# NFCAccessController.net
KiCad netlist of a schematic drawn in EAGLE
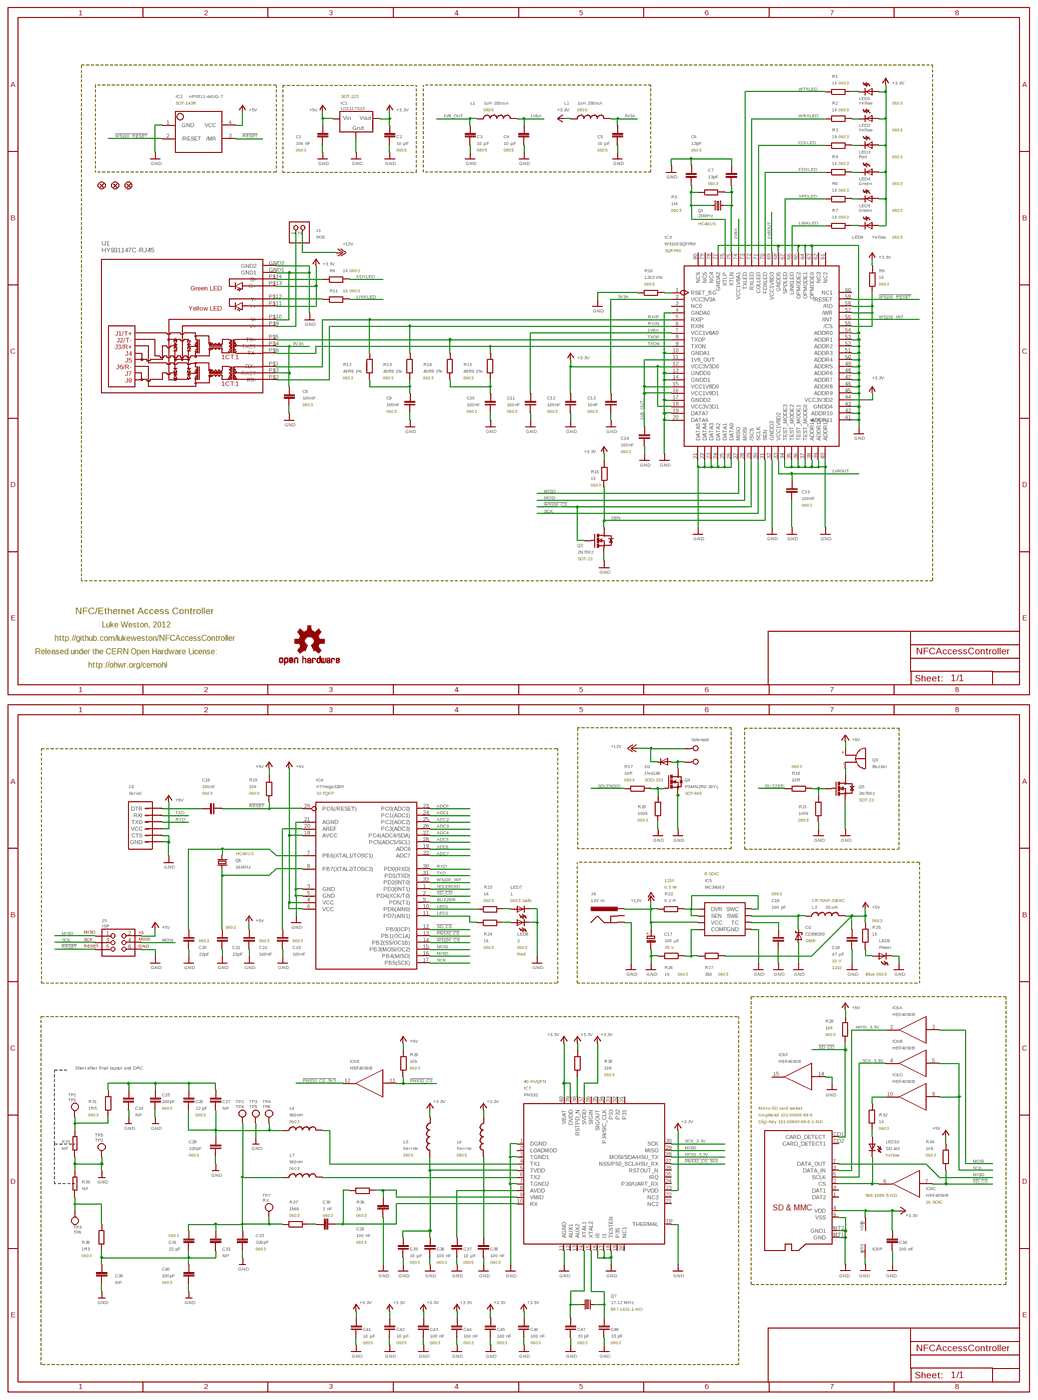
[diagram p0: schematic, sheet 1, overview]
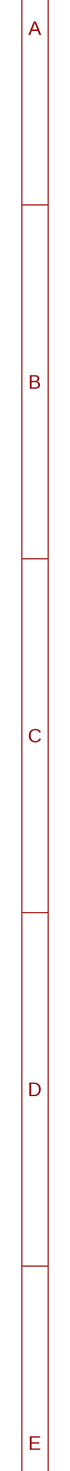
[diagram p1: schematic, sheet 1, part 1 of 4]
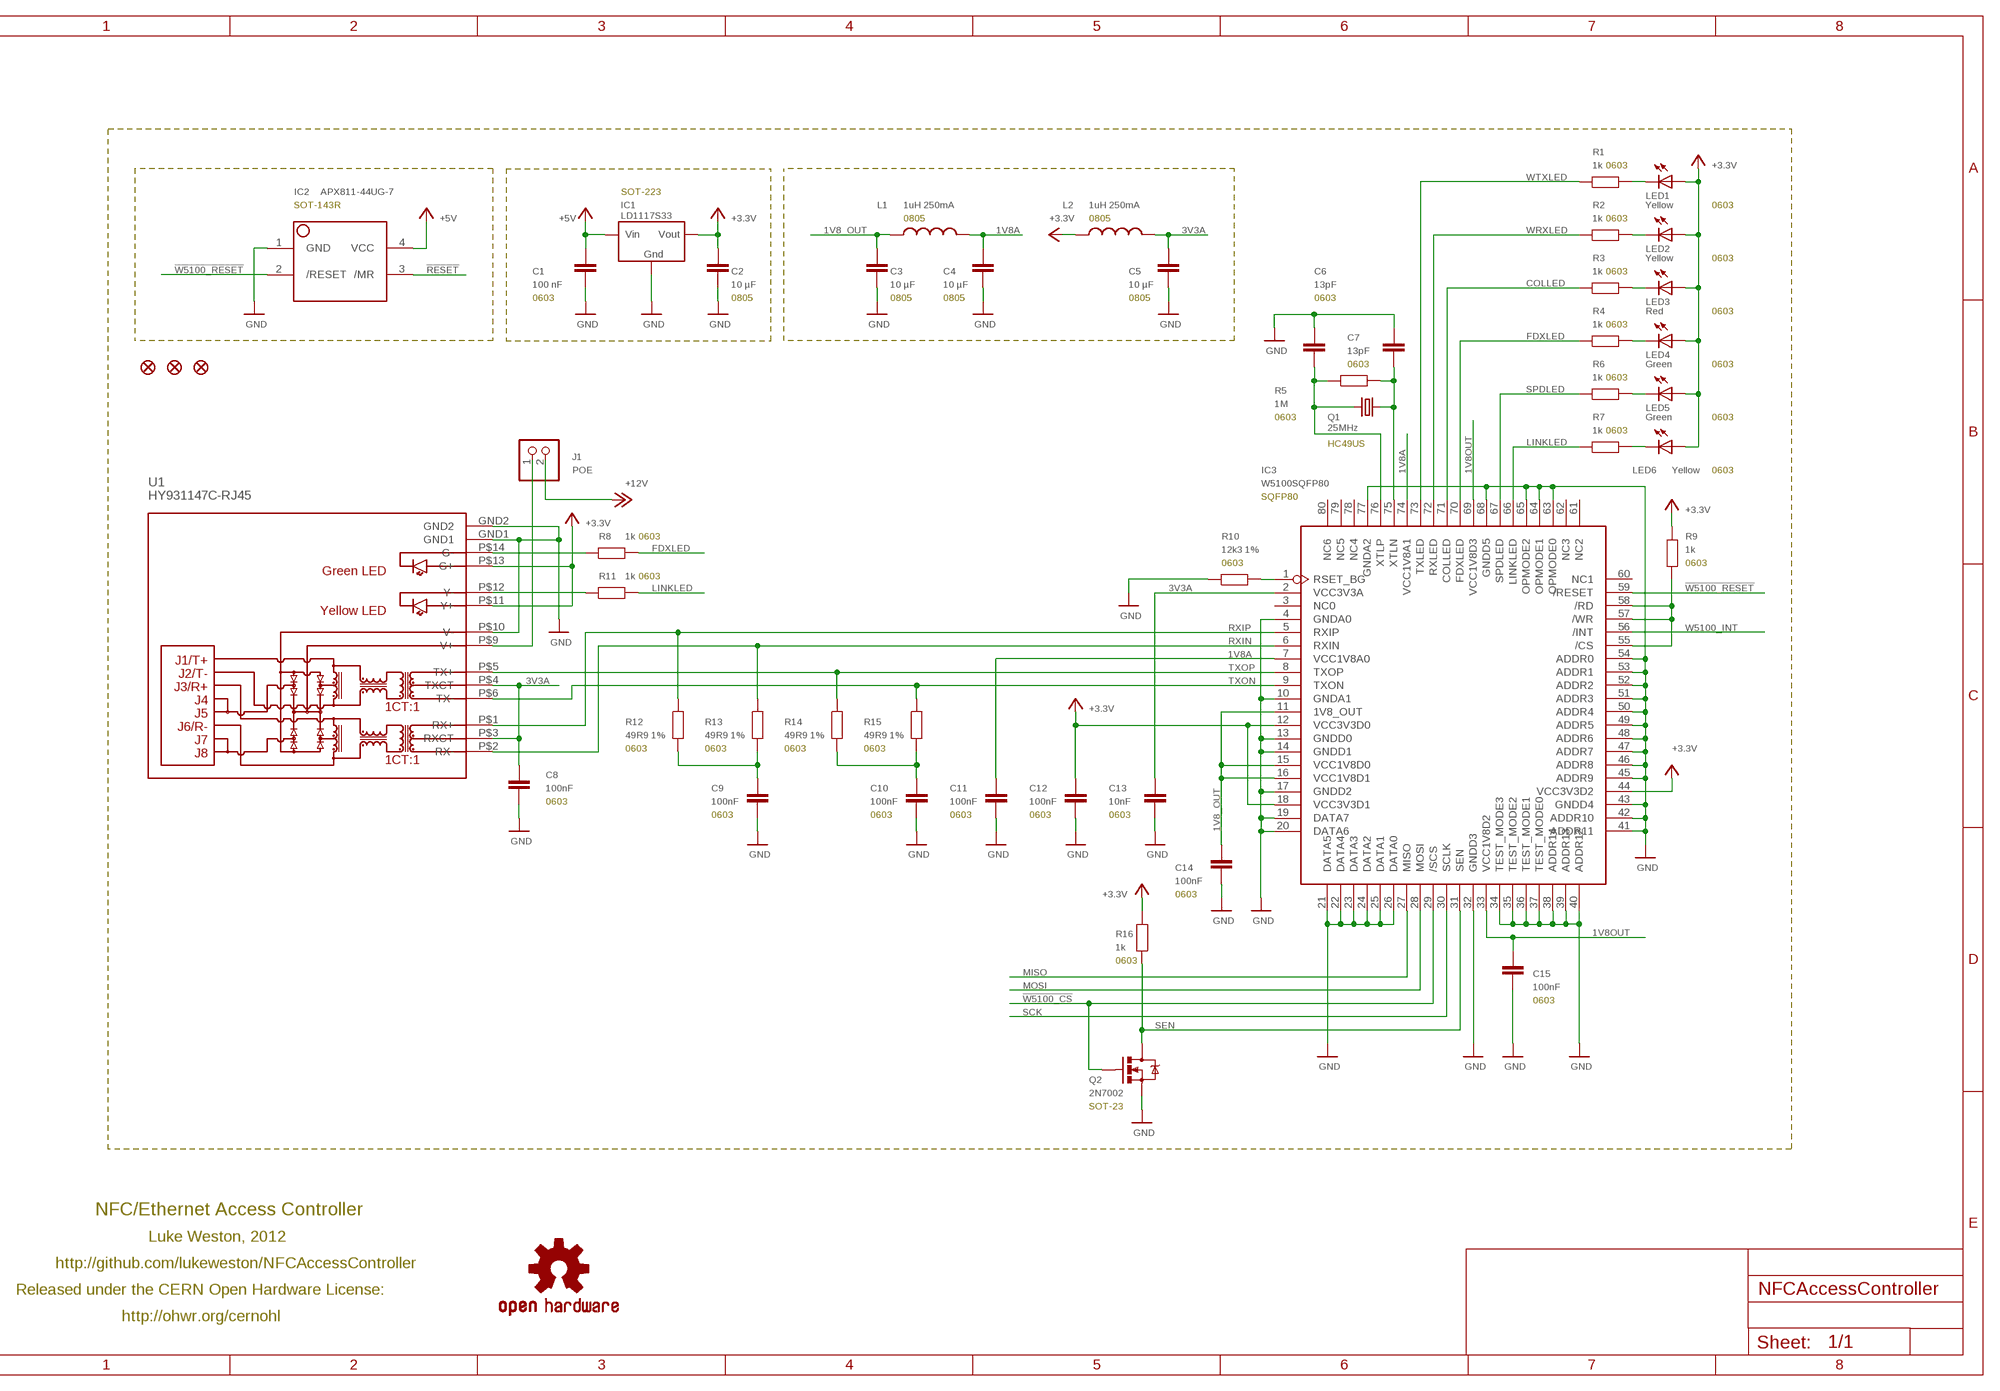
[diagram p2: schematic, sheet 1, part 2 of 4]
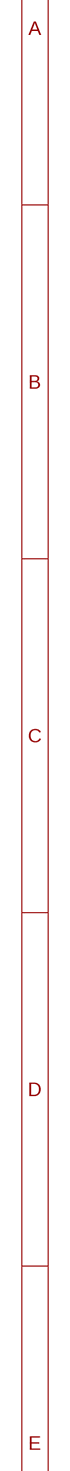
[diagram p3: schematic, sheet 1, part 3 of 4]
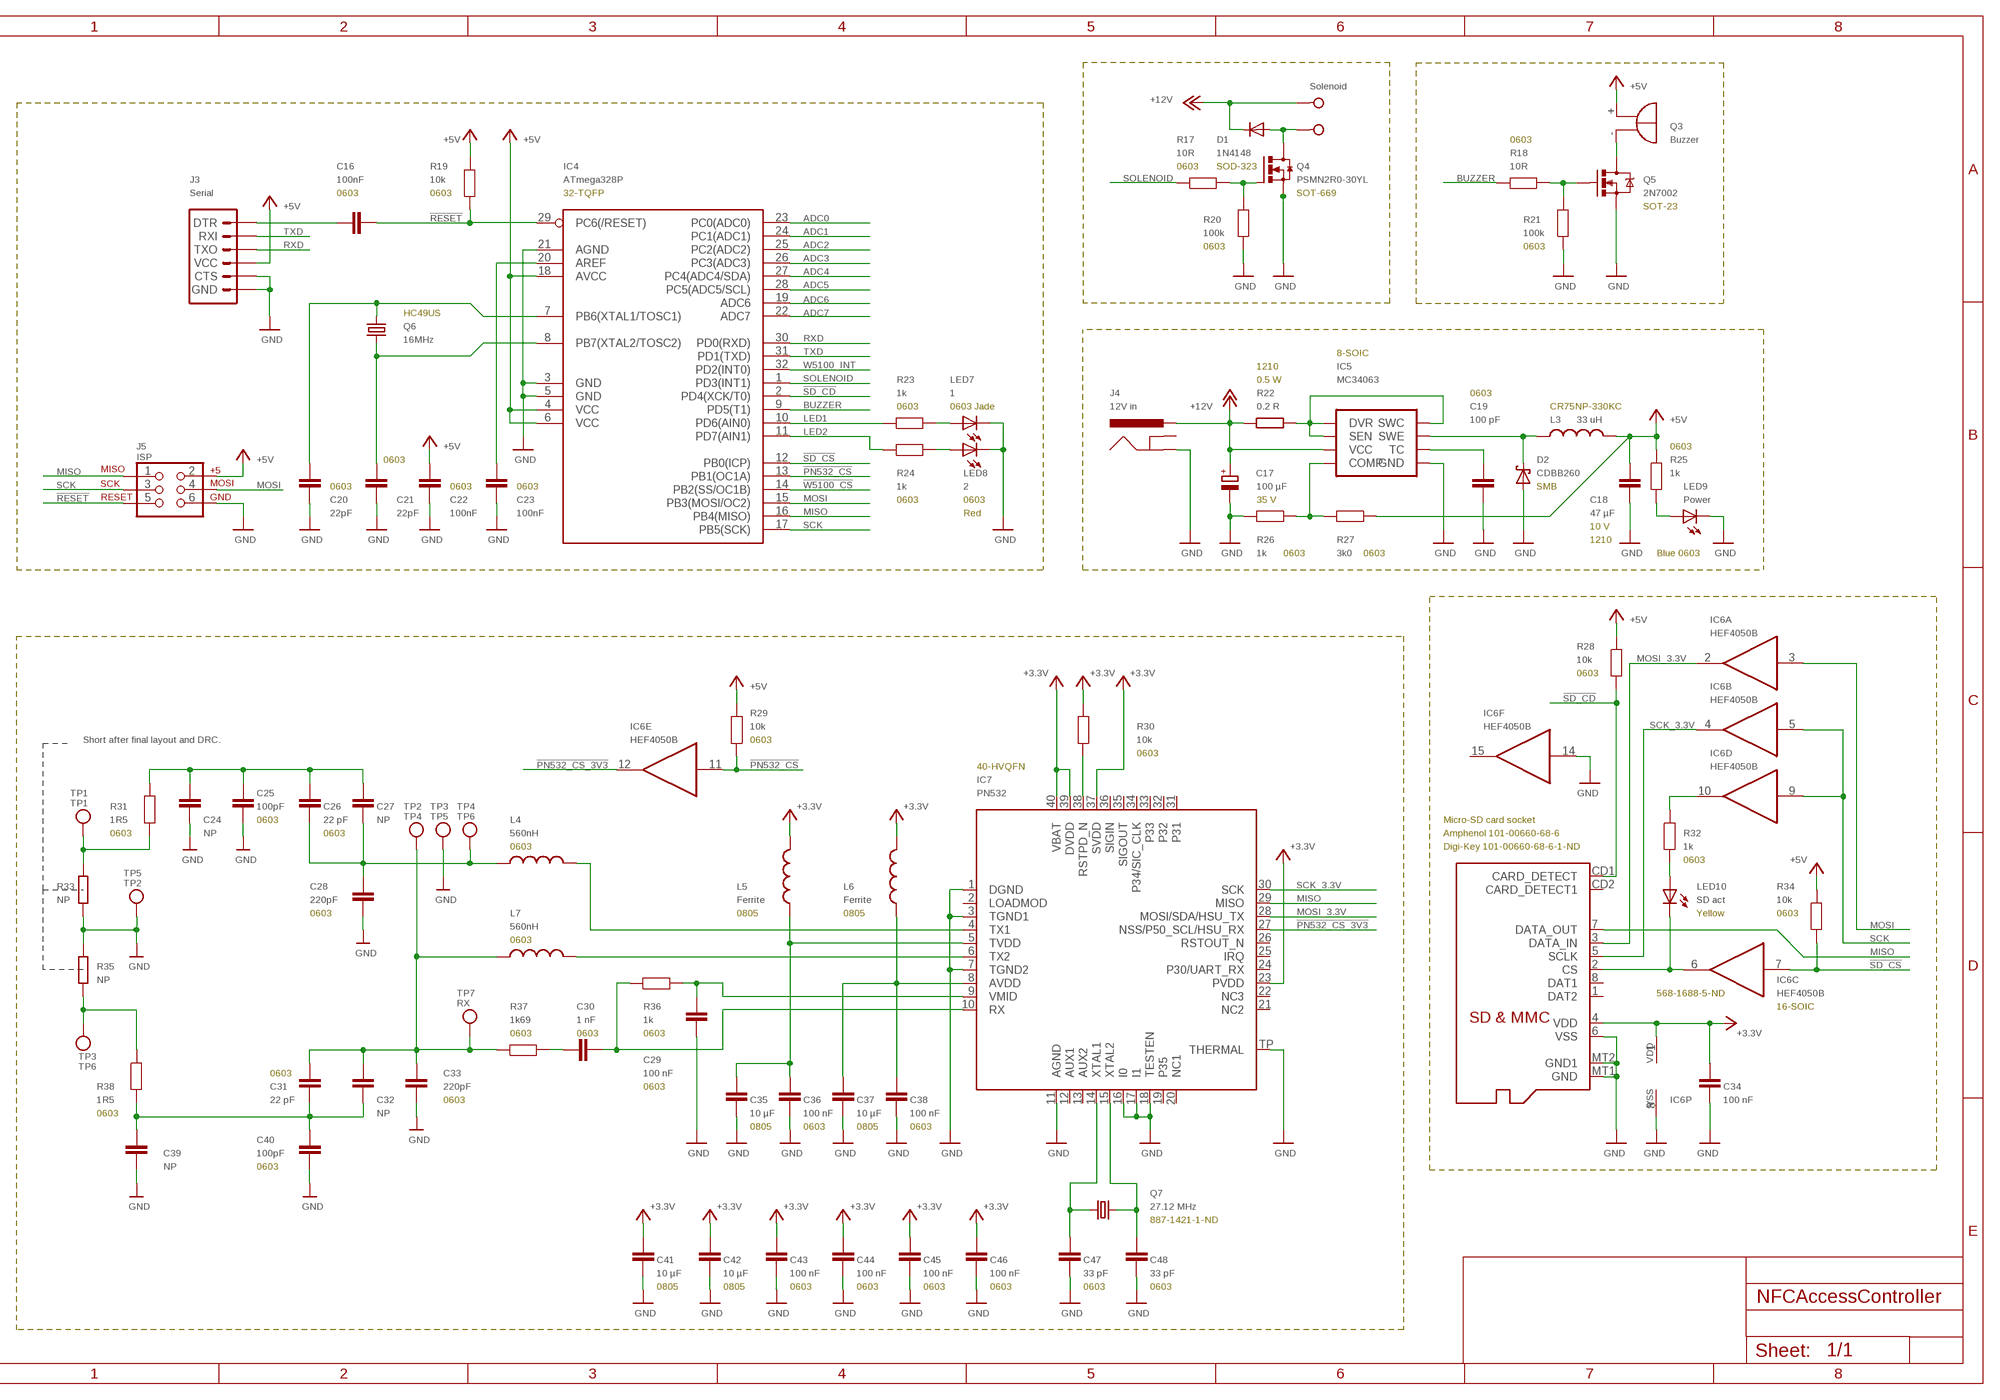
[diagram p4: schematic, sheet 1, part 4 of 4]

(export (version "E")
  (design (tool "Eeschema 10.0.6"))
  (components
    (comp (ref "C1")
      (value "100 nF")
      (footprint "eagle-import:0603")
      (libsource (lib "eagle-import") (part "CAP0603"))
    )
    (comp (ref "C2")
      (value "10 µF")
      (footprint "eagle-import:0805")
      (libsource (lib "eagle-import") (part "CAP0805"))
    )
    (comp (ref "C3")
      (value "10 µF")
      (footprint "eagle-import:0805")
      (libsource (lib "eagle-import") (part "CAP0805"))
    )
    (comp (ref "C4")
      (value "10 µF")
      (footprint "eagle-import:0805")
      (libsource (lib "eagle-import") (part "CAP0805"))
    )
    (comp (ref "C5")
      (value "10 µF")
      (footprint "eagle-import:0805")
      (libsource (lib "eagle-import") (part "CAP0805"))
    )
    (comp (ref "C6")
      (value "13pF")
      (footprint "eagle-import:0603")
      (libsource (lib "eagle-import") (part "CAP0603"))
    )
    (comp (ref "C7")
      (value "13pF")
      (footprint "eagle-import:0603")
      (libsource (lib "eagle-import") (part "CAP0603"))
    )
    (comp (ref "C8")
      (value "100nF")
      (footprint "eagle-import:0603")
      (libsource (lib "eagle-import") (part "CAP0603"))
    )
    (comp (ref "C9")
      (value "100nF")
      (footprint "eagle-import:0603")
      (libsource (lib "eagle-import") (part "CAP0603"))
    )
    (comp (ref "C10")
      (value "100nF")
      (footprint "eagle-import:0603")
      (libsource (lib "eagle-import") (part "CAP0603"))
    )
    (comp (ref "C11")
      (value "100nF")
      (footprint "eagle-import:0603")
      (libsource (lib "eagle-import") (part "CAP0603"))
    )
    (comp (ref "C12")
      (value "100nF")
      (footprint "eagle-import:0603")
      (libsource (lib "eagle-import") (part "CAP0603"))
    )
    (comp (ref "C13")
      (value "10nF")
      (footprint "eagle-import:0603")
      (libsource (lib "eagle-import") (part "CAP0603"))
    )
    (comp (ref "C14")
      (value "100nF")
      (footprint "eagle-import:0603")
      (libsource (lib "eagle-import") (part "CAP0603"))
    )
    (comp (ref "C15")
      (value "100nF")
      (footprint "eagle-import:0603")
      (libsource (lib "eagle-import") (part "CAP0603"))
    )
    (comp (ref "C16")
      (value "100nF")
      (footprint "eagle-import:0603")
      (libsource (lib "eagle-import") (part "CAP0603"))
    )
    (comp (ref "C17")
      (value "100 µF")
      (footprint "eagle-import:E2,5-6")
      (libsource (lib "eagle-import") (part "CPOL-EUE2.5-6"))
    )
    (comp (ref "C18")
      (value "47 µF")
      (footprint "eagle-import:C1210")
      (libsource (lib "eagle-import") (part "C-EUC1210"))
    )
    (comp (ref "C19")
      (value "100 pF")
      (footprint "eagle-import:0603")
      (libsource (lib "eagle-import") (part "CAP0603"))
    )
    (comp (ref "C20")
      (value "22pF")
      (footprint "eagle-import:0603")
      (libsource (lib "eagle-import") (part "CAP0603"))
    )
    (comp (ref "C21")
      (value "22pF")
      (footprint "eagle-import:0603")
      (libsource (lib "eagle-import") (part "CAP0603"))
    )
    (comp (ref "C22")
      (value "100nF")
      (footprint "eagle-import:0603")
      (libsource (lib "eagle-import") (part "CAP0603"))
    )
    (comp (ref "C23")
      (value "100nF")
      (footprint "eagle-import:0603")
      (libsource (lib "eagle-import") (part "CAP0603"))
    )
    (comp (ref "C24")
      (value "NP")
      (footprint "eagle-import:0603")
      (libsource (lib "eagle-import") (part "CAP0603"))
    )
    (comp (ref "C25")
      (value "100pF")
      (footprint "eagle-import:0603")
      (libsource (lib "eagle-import") (part "CAP0603"))
    )
    (comp (ref "C26")
      (value "22 pF")
      (footprint "eagle-import:0603")
      (libsource (lib "eagle-import") (part "CAP0603"))
    )
    (comp (ref "C27")
      (value "NP")
      (footprint "eagle-import:0603")
      (libsource (lib "eagle-import") (part "CAP0603"))
    )
    (comp (ref "C28")
      (value "220pF")
      (footprint "eagle-import:0603")
      (libsource (lib "eagle-import") (part "CAP0603"))
    )
    (comp (ref "C29")
      (value "100 nF")
      (footprint "eagle-import:0603")
      (libsource (lib "eagle-import") (part "CAP0603"))
    )
    (comp (ref "C30")
      (value "1 nF")
      (footprint "eagle-import:0603")
      (libsource (lib "eagle-import") (part "CAP0603"))
    )
    (comp (ref "C31")
      (value "22 pF")
      (footprint "eagle-import:0603")
      (libsource (lib "eagle-import") (part "CAP0603"))
    )
    (comp (ref "C32")
      (value "NP")
      (footprint "eagle-import:0603")
      (libsource (lib "eagle-import") (part "CAP0603"))
    )
    (comp (ref "C33")
      (value "220pF")
      (footprint "eagle-import:0603")
      (libsource (lib "eagle-import") (part "CAP0603"))
    )
    (comp (ref "C34")
      (value "100 nF")
      (footprint "eagle-import:0603")
      (libsource (lib "eagle-import") (part "CAP0603"))
    )
    (comp (ref "C35")
      (value "10 µF")
      (footprint "eagle-import:0805")
      (libsource (lib "eagle-import") (part "CAP0805"))
    )
    (comp (ref "C36")
      (value "100 nF")
      (footprint "eagle-import:0603")
      (libsource (lib "eagle-import") (part "CAP0603"))
    )
    (comp (ref "C37")
      (value "10 µF")
      (footprint "eagle-import:0805")
      (libsource (lib "eagle-import") (part "CAP0805"))
    )
    (comp (ref "C38")
      (value "100 nF")
      (footprint "eagle-import:0603")
      (libsource (lib "eagle-import") (part "CAP0603"))
    )
    (comp (ref "C39")
      (value "NP")
      (footprint "eagle-import:0603")
      (libsource (lib "eagle-import") (part "CAP0603"))
    )
    (comp (ref "C40")
      (value "100pF")
      (footprint "eagle-import:0603")
      (libsource (lib "eagle-import") (part "CAP0603"))
    )
    (comp (ref "C41")
      (value "10 µF")
      (footprint "eagle-import:0805")
      (libsource (lib "eagle-import") (part "CAP0805"))
    )
    (comp (ref "C42")
      (value "10 µF")
      (footprint "eagle-import:0805")
      (libsource (lib "eagle-import") (part "CAP0805"))
    )
    (comp (ref "C43")
      (value "100 nF")
      (footprint "eagle-import:0603")
      (libsource (lib "eagle-import") (part "CAP0603"))
    )
    (comp (ref "C44")
      (value "100 nF")
      (footprint "eagle-import:0603")
      (libsource (lib "eagle-import") (part "CAP0603"))
    )
    (comp (ref "C45")
      (value "100 nF")
      (footprint "eagle-import:0603")
      (libsource (lib "eagle-import") (part "CAP0603"))
    )
    (comp (ref "C46")
      (value "100 nF")
      (footprint "eagle-import:0603")
      (libsource (lib "eagle-import") (part "CAP0603"))
    )
    (comp (ref "C47")
      (value "33 pF")
      (footprint "eagle-import:0603")
      (libsource (lib "eagle-import") (part "CAP0603"))
    )
    (comp (ref "C48")
      (value "33 pF")
      (footprint "eagle-import:0603")
      (libsource (lib "eagle-import") (part "CAP0603"))
    )
    (comp (ref "D1")
      (value "1N4148")
      (footprint "eagle-import:SOD-323")
      (libsource (lib "eagle-import") (part "DIODESOD"))
    )
    (comp (ref "D2")
      (value "CDBB260")
      (footprint "eagle-import:SMB")
      (libsource (lib "eagle-import") (part "MBRS130LT3"))
    )
    (comp (ref "FID1")
      (value "FIDUCIAL1X2.5")
      (footprint "eagle-import:FIDUCIAL-1X2.5")
      (libsource (lib "eagle-import") (part "FIDUCIAL1X2.5"))
    )
    (comp (ref "FID2")
      (value "FIDUCIAL1X2.5")
      (footprint "eagle-import:FIDUCIAL-1X2.5")
      (libsource (lib "eagle-import") (part "FIDUCIAL1X2.5"))
    )
    (comp (ref "FID3")
      (value "FIDUCIAL1X2.5")
      (footprint "eagle-import:FIDUCIAL-1X2.5")
      (libsource (lib "eagle-import") (part "FIDUCIAL1X2.5"))
    )
    (comp (ref "IC1")
      (value "LD1117S33")
      (footprint "eagle-import:SOT223")
      (fields
        (field (name "MPN") "REG1117")
        (field (name "MPN_1") "REG1117")
        (field (name "OC_FARNELL") "1097566")
        (field (name "OC_NEWARK") "14P6981")
      )
      (libsource (lib "eagle-import") (part "REG1117"))
    )
    (comp (ref "IC2")
      (value "APX811-44UG-7")
      (footprint "eagle-import:SOT143-R")
      (libsource (lib "eagle-import") (part "APX81X-RESET-IC"))
    )
    (comp (ref "IC3")
      (value "W5100SQFP80")
      (footprint "eagle-import:SQFP80")
      (libsource (lib "eagle-import") (part "W5100SQFP80"))
    )
    (comp (ref "IC4")
      (value "ATmega328P")
      (footprint "eagle-import:TQFP32-08")
      (libsource (lib "eagle-import") (part "AVR-MEGA8-AI"))
    )
    (comp (ref "IC5")
      (value "MC34063")
      (footprint "eagle-import:SO08")
      (libsource (lib "eagle-import") (part "MC34063SMD"))
    )
    (comp (ref "IC6")
      (value "HEF4050B")
      (footprint "eagle-import:SO16")
      (libsource (lib "eagle-import") (part "4050D"))
    )
    (comp (ref "IC7")
      (value "PN532")
      (footprint "eagle-import:HVQFN40-6X6")
      (libsource (lib "eagle-import") (part "PN532"))
    )
    (comp (ref "J1")
      (value "POE")
      (footprint "eagle-import:1X02")
      (libsource (lib "eagle-import") (part "PINHD-1X2"))
    )
    (comp (ref "J2")
      (value "Solenoid")
      (footprint "eagle-import:W237-132")
      (fields (field (name "OC_FARNELL") "unknown") (field (name "OC_NEWARK") "unknown"))
      (libsource (lib "eagle-import") (part "W237-02P"))
    )
    (comp (ref "J3")
      (value "Serial")
      (footprint "eagle-import:1X06_LONGPADS")
      (libsource (lib "eagle-import") (part "ARDUINO_SERIAL_PROGRAMLONGPADS"))
    )
    (comp (ref "J4")
      (value "12V in")
      (footprint "eagle-import:POWER_JACK_SLOT")
      (libsource (lib "eagle-import") (part "POWER_JACKSLT"))
    )
    (comp (ref "J5")
      (value "ISP")
      (footprint "eagle-import:2X3-NS")
      (libsource (lib "eagle-import") (part "AVR_SPI_PRG_6NS"))
    )
    (comp (ref "J6")
      (value "MicroSD Card")
      (footprint "eagle-import:ADAFRUIT_MICROSD")
      (libsource (lib "eagle-import") (part "ADAFRUIT_MICROSD"))
    )
    (comp (ref "L1")
      (value "1uH 250mA")
      (footprint "eagle-import:L2012C")
      (libsource (lib "eagle-import") (part "L-USL2012C"))
    )
    (comp (ref "L2")
      (value "1uH 250mA")
      (footprint "eagle-import:L2012C")
      (libsource (lib "eagle-import") (part "L-USL2012C"))
    )
    (comp (ref "L3")
      (value "33 uH")
      (footprint "eagle-import:CR75")
      (libsource (lib "eagle-import") (part "INDUCTORCR75"))
    )
    (comp (ref "L4")
      (value "560nH")
      (footprint "eagle-import:0603")
      (libsource (lib "eagle-import") (part "microbuilder_INDUCTOR0603"))
    )
    (comp (ref "L5")
      (value "Ferrite")
      (footprint "eagle-import:0805-LARGE")
      (libsource (lib "eagle-import") (part "INDUCTOR0805-LARGE"))
    )
    (comp (ref "L6")
      (value "Ferrite")
      (footprint "eagle-import:0805-LARGE")
      (libsource (lib "eagle-import") (part "INDUCTOR0805-LARGE"))
    )
    (comp (ref "L7")
      (value "560nH")
      (footprint "eagle-import:0603")
      (libsource (lib "eagle-import") (part "microbuilder_INDUCTOR0603"))
    )
    (comp (ref "LED1")
      (value "Yellow")
      (footprint "eagle-import:LED-0603")
      (libsource (lib "eagle-import") (part "LED0603"))
    )
    (comp (ref "LED2")
      (value "Yellow")
      (footprint "eagle-import:LED-0603")
      (libsource (lib "eagle-import") (part "LED0603"))
    )
    (comp (ref "LED3")
      (value "Red")
      (footprint "eagle-import:LED-0603")
      (libsource (lib "eagle-import") (part "LED0603"))
    )
    (comp (ref "LED4")
      (value "Green")
      (footprint "eagle-import:LED-0603")
      (libsource (lib "eagle-import") (part "LED0603"))
    )
    (comp (ref "LED5")
      (value "Green")
      (footprint "eagle-import:LED-0603")
      (libsource (lib "eagle-import") (part "LED0603"))
    )
    (comp (ref "LED6")
      (value "Yellow")
      (footprint "eagle-import:LED-0603")
      (libsource (lib "eagle-import") (part "LED0603"))
    )
    (comp (ref "LED7")
      (value "1")
      (footprint "eagle-import:LED-0603")
      (libsource (lib "eagle-import") (part "LED0603"))
    )
    (comp (ref "LED8")
      (value "2")
      (footprint "eagle-import:LED-0603")
      (libsource (lib "eagle-import") (part "LED0603"))
    )
    (comp (ref "LED9")
      (value "Power")
      (footprint "eagle-import:LED-0603")
      (libsource (lib "eagle-import") (part "LED0603"))
    )
    (comp (ref "LED10")
      (value "SD act")
      (footprint "eagle-import:LED-0603")
      (libsource (lib "eagle-import") (part "LED0603"))
    )
    (comp (ref "Q1")
      (value "25MHz")
      (footprint "eagle-import:HC49U-V")
      (libsource (lib "eagle-import") (part "freetronics-master-v1_CRYSTALHC49UV"))
    )
    (comp (ref "Q2")
      (value "2N7002")
      (footprint "eagle-import:SOT23-3")
      (libsource (lib "eagle-import") (part "MOSFET-NCHANNELSMD"))
    )
    (comp (ref "Q3")
      (value "Buzzer")
      (footprint "eagle-import:F_TMB")
      (libsource (lib "eagle-import") (part "F/TMB"))
    )
    (comp (ref "Q4")
      (value "PSMN2R0-30YL")
      (footprint "eagle-import:SOT669")
      (libsource (lib "eagle-import") (part "PH7030L"))
    )
    (comp (ref "Q5")
      (value "2N7002")
      (footprint "eagle-import:SOT23-3")
      (libsource (lib "eagle-import") (part "freetronics-master-v1_MOSFET-NCHANNELSMD"))
    )
    (comp (ref "Q6")
      (value "16MHz")
      (footprint "eagle-import:HC49U-V")
      (libsource (lib "eagle-import") (part "freetronics-master-v1_CRYSTALHC49UV"))
    )
    (comp (ref "Q7")
      (value "27.12 MHz")
      (footprint "eagle-import:CRYSTAL-SMD-5X3")
      (libsource (lib "eagle-import") (part "CRYSTAL5X3"))
    )
    (comp (ref "R1")
      (value "1k")
      (footprint "eagle-import:0603")
      (libsource (lib "eagle-import") (part "RESISTOR0603"))
    )
    (comp (ref "R2")
      (value "1k")
      (footprint "eagle-import:0603")
      (libsource (lib "eagle-import") (part "RESISTOR0603"))
    )
    (comp (ref "R3")
      (value "1k")
      (footprint "eagle-import:0603")
      (libsource (lib "eagle-import") (part "RESISTOR0603"))
    )
    (comp (ref "R4")
      (value "1k")
      (footprint "eagle-import:0603")
      (libsource (lib "eagle-import") (part "RESISTOR0603"))
    )
    (comp (ref "R5")
      (value "1M")
      (footprint "eagle-import:0603")
      (libsource (lib "eagle-import") (part "RESISTOR0603"))
    )
    (comp (ref "R6")
      (value "1k")
      (footprint "eagle-import:0603")
      (libsource (lib "eagle-import") (part "RESISTOR0603"))
    )
    (comp (ref "R7")
      (value "1k")
      (footprint "eagle-import:0603")
      (libsource (lib "eagle-import") (part "RESISTOR0603"))
    )
    (comp (ref "R8")
      (value "1k")
      (footprint "eagle-import:0603")
      (libsource (lib "eagle-import") (part "RESISTOR0603"))
    )
    (comp (ref "R9")
      (value "1k")
      (footprint "eagle-import:0603")
      (libsource (lib "eagle-import") (part "RESISTOR0603"))
    )
    (comp (ref "R10")
      (value "12k3 1%")
      (footprint "eagle-import:0603")
      (libsource (lib "eagle-import") (part "RESISTOR0603"))
    )
    (comp (ref "R11")
      (value "1k")
      (footprint "eagle-import:0603")
      (libsource (lib "eagle-import") (part "RESISTOR0603"))
    )
    (comp (ref "R12")
      (value "49R9 1%")
      (footprint "eagle-import:0603")
      (libsource (lib "eagle-import") (part "RESISTOR0603"))
    )
    (comp (ref "R13")
      (value "49R9 1%")
      (footprint "eagle-import:0603")
      (libsource (lib "eagle-import") (part "RESISTOR0603"))
    )
    (comp (ref "R14")
      (value "49R9 1%")
      (footprint "eagle-import:0603")
      (libsource (lib "eagle-import") (part "RESISTOR0603"))
    )
    (comp (ref "R15")
      (value "49R9 1%")
      (footprint "eagle-import:0603")
      (libsource (lib "eagle-import") (part "RESISTOR0603"))
    )
    (comp (ref "R16")
      (value "1k")
      (footprint "eagle-import:0603")
      (libsource (lib "eagle-import") (part "RESISTOR0603"))
    )
    (comp (ref "R17")
      (value "10R")
      (footprint "eagle-import:0603")
      (libsource (lib "eagle-import") (part "RESISTOR0603"))
    )
    (comp (ref "R18")
      (value "10R")
      (footprint "eagle-import:0603")
      (libsource (lib "eagle-import") (part "RESISTOR0603"))
    )
    (comp (ref "R19")
      (value "10k")
      (footprint "eagle-import:0603")
      (libsource (lib "eagle-import") (part "RESISTOR0603"))
    )
    (comp (ref "R20")
      (value "100k")
      (footprint "eagle-import:0603")
      (libsource (lib "eagle-import") (part "RESISTOR0603"))
    )
    (comp (ref "R21")
      (value "100k")
      (footprint "eagle-import:0603")
      (libsource (lib "eagle-import") (part "RESISTOR0603"))
    )
    (comp (ref "R22")
      (value "0.2 R")
      (footprint "eagle-import:R1210")
      (libsource (lib "eagle-import") (part "R-EU_R1210"))
    )
    (comp (ref "R23")
      (value "1k")
      (footprint "eagle-import:0603")
      (libsource (lib "eagle-import") (part "RESISTOR0603"))
    )
    (comp (ref "R24")
      (value "1k")
      (footprint "eagle-import:0603")
      (libsource (lib "eagle-import") (part "RESISTOR0603"))
    )
    (comp (ref "R25")
      (value "1k")
      (footprint "eagle-import:0603")
      (libsource (lib "eagle-import") (part "RESISTOR0603"))
    )
    (comp (ref "R26")
      (value "1k")
      (footprint "eagle-import:0603")
      (libsource (lib "eagle-import") (part "RESISTOR0603"))
    )
    (comp (ref "R27")
      (value "3k0")
      (footprint "eagle-import:0603")
      (libsource (lib "eagle-import") (part "RESISTOR0603"))
    )
    (comp (ref "R28")
      (value "10k")
      (footprint "eagle-import:0603")
      (libsource (lib "eagle-import") (part "RESISTOR0603"))
    )
    (comp (ref "R29")
      (value "10k")
      (footprint "eagle-import:0603")
      (libsource (lib "eagle-import") (part "RESISTOR0603"))
    )
    (comp (ref "R30")
      (value "10k")
      (footprint "eagle-import:0603")
      (libsource (lib "eagle-import") (part "RESISTOR0603"))
    )
    (comp (ref "R31")
      (value "1R5")
      (footprint "eagle-import:0603")
      (libsource (lib "eagle-import") (part "RESISTOR0603"))
    )
    (comp (ref "R32")
      (value "1k")
      (footprint "eagle-import:0603")
      (libsource (lib "eagle-import") (part "RESISTOR0603"))
    )
    (comp (ref "R33")
      (value "NP")
      (footprint "eagle-import:R0201")
      (libsource (lib "eagle-import") (part "R-EU_R0201"))
    )
    (comp (ref "R34")
      (value "10k")
      (footprint "eagle-import:0603")
      (libsource (lib "eagle-import") (part "RESISTOR0603"))
    )
    (comp (ref "R35")
      (value "NP")
      (footprint "eagle-import:R0201")
      (libsource (lib "eagle-import") (part "R-EU_R0201"))
    )
    (comp (ref "R36")
      (value "1k")
      (footprint "eagle-import:0603")
      (libsource (lib "eagle-import") (part "RESISTOR0603"))
    )
    (comp (ref "R37")
      (value "1k69")
      (footprint "eagle-import:0603")
      (libsource (lib "eagle-import") (part "RESISTOR0603"))
    )
    (comp (ref "R38")
      (value "1R5")
      (footprint "eagle-import:0603")
      (libsource (lib "eagle-import") (part "RESISTOR0603"))
    )
    (comp (ref "S$1")
      (value "OSHW-LOGOS")
      (footprint "eagle-import:OSHW-LOGO-S")
      (libsource (lib "eagle-import") (part "OSHW-LOGOS"))
    )
    (comp (ref "TP1")
      (value "TP1")
      (footprint "eagle-import:TESTPOINT_PAD_2MM")
      (libsource (lib "eagle-import") (part "TESTPOINTPAD"))
    )
    (comp (ref "TP2")
      (value "TP4")
      (footprint "eagle-import:TESTPOINT_PAD_2MM")
      (libsource (lib "eagle-import") (part "TESTPOINTPAD"))
    )
    (comp (ref "TP3")
      (value "TP5")
      (footprint "eagle-import:TESTPOINT_PAD_2MM")
      (libsource (lib "eagle-import") (part "TESTPOINTPAD"))
    )
    (comp (ref "TP4")
      (value "TP6")
      (footprint "eagle-import:TESTPOINT_PAD_2MM")
      (libsource (lib "eagle-import") (part "TESTPOINTPAD"))
    )
    (comp (ref "TP5")
      (value "TP2")
      (footprint "eagle-import:TESTPOINT_PAD_2MM")
      (libsource (lib "eagle-import") (part "TESTPOINTPAD"))
    )
    (comp (ref "TP6")
      (value "TP3")
      (footprint "eagle-import:TESTPOINT_PAD_2MM")
      (libsource (lib "eagle-import") (part "TESTPOINTPAD"))
    )
    (comp (ref "TP7")
      (value "RX")
      (footprint "eagle-import:TESTPOINT_PAD_2MM")
      (libsource (lib "eagle-import") (part "TESTPOINTPAD"))
    )
    (comp (ref "U1")
      (value "HY931147C-RJ45")
      (footprint "eagle-import:HY931147C")
      (libsource (lib "eagle-import") (part "HY931147C-RJ45"))
    )
  )
  (nets
    (net (code "1") (name "+3.3V") (class "Default")
      (node (ref "C12") (pin "1") (pinfunction "1_1") (pintype "passive"))
      (node (ref "C2") (pin "1") (pinfunction "1_1") (pintype "passive"))
      (node (ref "C34") (pin "1") (pinfunction "1_1") (pintype "passive"))
      (node (ref "C41") (pin "1") (pinfunction "1_1") (pintype "passive"))
      (node (ref "C42") (pin "1") (pinfunction "1_1") (pintype "passive"))
      (node (ref "C43") (pin "1") (pinfunction "1_1") (pintype "passive"))
      (node (ref "C44") (pin "1") (pinfunction "1_1") (pintype "passive"))
      (node (ref "C45") (pin "1") (pinfunction "1_1") (pintype "passive"))
      (node (ref "C46") (pin "1") (pinfunction "1_1") (pintype "passive"))
      (node (ref "IC1") (pin "2") (pinfunction "VOUT_2") (pintype "output"))
      (node (ref "IC3") (pin "12") (pinfunction "VCC3V3D0_12") (pintype "bidirectional"))
      (node (ref "IC3") (pin "18") (pinfunction "VCC3V3D1_18") (pintype "bidirectional"))
      (node (ref "IC3") (pin "44") (pinfunction "VCC3V3D2_44") (pintype "bidirectional"))
      (node (ref "IC6") (pin "1") (pinfunction "VDD_1") (pintype "power_in"))
      (node (ref "IC7") (pin "23") (pinfunction "PVDD_23") (pintype "bidirectional"))
      (node (ref "IC7") (pin "37") (pinfunction "SVDD_37") (pintype "bidirectional"))
      (node (ref "IC7") (pin "39") (pinfunction "DVDD_39") (pintype "bidirectional"))
      (node (ref "IC7") (pin "40") (pinfunction "VBAT_40") (pintype "bidirectional"))
      (node (ref "J6") (pin "4") (pinfunction "VDD_4") (pintype "power_in"))
      (node (ref "L2") (pin "1") (pinfunction "1_1") (pintype "passive"))
      (node (ref "L5") (pin "2") (pinfunction "2_2") (pintype "passive"))
      (node (ref "L6") (pin "2") (pinfunction "2_2") (pintype "passive"))
      (node (ref "LED1") (pin "A") (pinfunction "A_A") (pintype "passive"))
      (node (ref "LED2") (pin "A") (pinfunction "A_A") (pintype "passive"))
      (node (ref "LED3") (pin "A") (pinfunction "A_A") (pintype "passive"))
      (node (ref "LED4") (pin "A") (pinfunction "A_A") (pintype "passive"))
      (node (ref "LED5") (pin "A") (pinfunction "A_A") (pintype "passive"))
      (node (ref "LED6") (pin "A") (pinfunction "A_A") (pintype "passive"))
      (node (ref "R16") (pin "1") (pinfunction "1_1") (pintype "passive"))
      (node (ref "R30") (pin "1") (pinfunction "1_1") (pintype "passive"))
      (node (ref "R9") (pin "1") (pinfunction "1_1") (pintype "passive"))
      (node (ref "U1") (pin "P$11") (pinfunction "Y+_P$11") (pintype "bidirectional"))
      (node (ref "U1") (pin "P$13") (pinfunction "G+_P$13") (pintype "bidirectional"))
    )
    (net (code "2") (name "+5V") (class "Default")
      (node (ref "C1") (pin "1") (pinfunction "1_1") (pintype "passive"))
      (node (ref "C18") (pin "1") (pinfunction "1_1") (pintype "passive"))
      (node (ref "C22") (pin "1") (pinfunction "1_1") (pintype "passive"))
      (node (ref "IC1") (pin "3") (pinfunction "VIN_3") (pintype "input"))
      (node (ref "IC2") (pin "4") (pinfunction "VCC_4") (pintype "power_in"))
      (node (ref "IC4") (pin "18") (pinfunction "AVCC_18") (pintype "bidirectional"))
      (node (ref "IC4") (pin "4") (pinfunction "VCC_4") (pintype "bidirectional"))
      (node (ref "IC4") (pin "6") (pinfunction "VCC_6") (pintype "bidirectional"))
      (node (ref "J3") (pin "4") (pinfunction "VCC_4") (pintype "passive"))
      (node (ref "J5") (pin "2") (pinfunction "2_2") (pintype "passive"))
      (node (ref "L3") (pin "P$2") (pinfunction "2_P$2") (pintype "passive"))
      (node (ref "Q3") (pin "+") (pinfunction "+_+") (pintype "passive"))
      (node (ref "R19") (pin "2") (pinfunction "2_2") (pintype "passive"))
      (node (ref "R25") (pin "2") (pinfunction "2_2") (pintype "passive"))
      (node (ref "R27") (pin "1") (pinfunction "1_1") (pintype "passive"))
      (node (ref "R28") (pin "2") (pinfunction "2_2") (pintype "passive"))
      (node (ref "R29") (pin "1") (pinfunction "1_1") (pintype "passive"))
      (node (ref "R34") (pin "2") (pinfunction "2_2") (pintype "passive"))
    )
    (net (code "3") (name "+12V") (class "Default")
      (node (ref "C17") (pin "+") (pinfunction "+_+") (pintype "passive"))
      (node (ref "D1") (pin "1") (pinfunction "C_1") (pintype "passive"))
      (node (ref "IC5") (pin "6") (pinfunction "VCC_6") (pintype "bidirectional"))
      (node (ref "J1") (pin "2") (pinfunction "2_2") (pintype "passive"))
      (node (ref "J2") (pin "1") (pinfunction "KL_1") (pintype "passive"))
      (node (ref "J4") (pin "PWR") (pinfunction "PWR_PWR") (pintype "bidirectional"))
      (node (ref "R22") (pin "1") (pinfunction "1_1") (pintype "passive"))
    )
    (net (code "4") (name "/1V8A") (class "Default")
      (node (ref "C11") (pin "1") (pinfunction "1_1") (pintype "passive"))
      (node (ref "C4") (pin "1") (pinfunction "1_1") (pintype "passive"))
      (node (ref "IC3") (pin "7") (pinfunction "VCC1V8A0_7") (pintype "bidirectional"))
      (node (ref "IC3") (pin "74") (pinfunction "VCC1V8A1_74") (pintype "bidirectional"))
      (node (ref "L1") (pin "2") (pinfunction "2_2") (pintype "passive"))
    )
    (net (code "5") (name "/1V8OUT") (class "Default")
      (node (ref "C15") (pin "1") (pinfunction "1_1") (pintype "passive"))
      (node (ref "IC3") (pin "33") (pinfunction "VCC1V8D2_33") (pintype "bidirectional"))
      (node (ref "IC3") (pin "69") (pinfunction "VCC1V8D3_69") (pintype "bidirectional"))
    )
    (net (code "6") (name "/1V8_OUT") (class "Default")
      (node (ref "C14") (pin "1") (pinfunction "1_1") (pintype "passive"))
      (node (ref "C3") (pin "1") (pinfunction "1_1") (pintype "passive"))
      (node (ref "IC3") (pin "11") (pinfunction "1V8_OUT_11") (pintype "bidirectional"))
      (node (ref "IC3") (pin "15") (pinfunction "VCC1V8D0_15") (pintype "bidirectional"))
      (node (ref "IC3") (pin "16") (pinfunction "VCC1V8D1_16") (pintype "bidirectional"))
      (node (ref "L1") (pin "1") (pinfunction "1_1") (pintype "passive"))
    )
    (net (code "7") (name "/3V3A") (class "Default")
      (node (ref "C13") (pin "1") (pinfunction "1_1") (pintype "passive"))
      (node (ref "C5") (pin "1") (pinfunction "1_1") (pintype "passive"))
      (node (ref "C8") (pin "1") (pinfunction "1_1") (pintype "passive"))
      (node (ref "IC3") (pin "2") (pinfunction "VCC3V3A_2") (pintype "bidirectional"))
      (node (ref "L2") (pin "2") (pinfunction "2_2") (pintype "passive"))
      (node (ref "U1") (pin "P$3") (pinfunction "RXCT_P$3") (pintype "bidirectional"))
      (node (ref "U1") (pin "P$4") (pinfunction "TXCT_P$4") (pintype "bidirectional"))
    )
    (net (code "8") (name "/ADC0") (class "Default")
      (node (ref "IC4") (pin "23") (pinfunction "PC0(ADC0)_23") (pintype "bidirectional"))
    )
    (net (code "9") (name "/ADC1") (class "Default")
      (node (ref "IC4") (pin "24") (pinfunction "PC1(ADC1)_24") (pintype "bidirectional"))
    )
    (net (code "10") (name "/ADC2") (class "Default")
      (node (ref "IC4") (pin "25") (pinfunction "PC2(ADC2)_25") (pintype "bidirectional"))
    )
    (net (code "11") (name "/ADC3") (class "Default")
      (node (ref "IC4") (pin "26") (pinfunction "PC3(ADC3)_26") (pintype "bidirectional"))
    )
    (net (code "12") (name "/ADC4") (class "Default")
      (node (ref "IC4") (pin "27") (pinfunction "PC4(ADC4/SDA)_27") (pintype "bidirectional"))
    )
    (net (code "13") (name "/ADC5") (class "Default")
      (node (ref "IC4") (pin "28") (pinfunction "PC5(ADC5/SCL)_28") (pintype "bidirectional"))
    )
    (net (code "14") (name "/ADC6") (class "Default")
      (node (ref "IC4") (pin "19") (pinfunction "ADC6_19") (pintype "bidirectional"))
    )
    (net (code "15") (name "/ADC7") (class "Default")
      (node (ref "IC4") (pin "22") (pinfunction "ADC7_22") (pintype "bidirectional"))
    )
    (net (code "16") (name "/BUZZER") (class "Default")
      (node (ref "IC4") (pin "9") (pinfunction "PD5(T1)_9") (pintype "bidirectional"))
      (node (ref "R18") (pin "1") (pinfunction "1_1") (pintype "passive"))
    )
    (net (code "17") (name "/COLLED") (class "Default")
      (node (ref "IC3") (pin "71") (pinfunction "COLLED_71") (pintype "bidirectional"))
      (node (ref "R3") (pin "1") (pinfunction "1_1") (pintype "passive"))
    )
    (net (code "18") (name "/FDXLED") (class "Default")
      (node (ref "IC3") (pin "70") (pinfunction "FDXLED_70") (pintype "bidirectional"))
      (node (ref "R4") (pin "1") (pinfunction "1_1") (pintype "passive"))
      (node (ref "R8") (pin "2") (pinfunction "2_2") (pintype "passive"))
    )
    (net (code "19") (name "/LED1") (class "Default")
      (node (ref "IC4") (pin "10") (pinfunction "PD6(AIN0)_10") (pintype "bidirectional"))
      (node (ref "R23") (pin "1") (pinfunction "1_1") (pintype "passive"))
    )
    (net (code "20") (name "/LED2") (class "Default")
      (node (ref "IC4") (pin "11") (pinfunction "PD7(AIN1)_11") (pintype "bidirectional"))
      (node (ref "R24") (pin "1") (pinfunction "1_1") (pintype "passive"))
    )
    (net (code "21") (name "/LINKLED") (class "Default")
      (node (ref "IC3") (pin "66") (pinfunction "LINKLED_66") (pintype "bidirectional"))
      (node (ref "R11") (pin "2") (pinfunction "2_2") (pintype "passive"))
      (node (ref "R7") (pin "1") (pinfunction "1_1") (pintype "passive"))
    )
    (net (code "22") (name "/MISO") (class "Default")
      (node (ref "IC3") (pin "27") (pinfunction "MISO_27") (pintype "bidirectional"))
      (node (ref "IC4") (pin "16") (pinfunction "PB4(MISO)_16") (pintype "bidirectional"))
      (node (ref "IC7") (pin "29") (pinfunction "MISO_29") (pintype "bidirectional"))
      (node (ref "J5") (pin "1") (pinfunction "1_1") (pintype "passive"))
      (node (ref "J6") (pin "7") (pinfunction "DATA_OUT_7") (pintype "output"))
    )
    (net (code "23") (name "/MOSI") (class "Default")
      (node (ref "IC3") (pin "28") (pinfunction "MOSI_28") (pintype "bidirectional"))
      (node (ref "IC4") (pin "15") (pinfunction "PB3(MOSI/OC2)_15") (pintype "bidirectional"))
      (node (ref "IC6") (pin "3") (pinfunction "I_3") (pintype "input"))
      (node (ref "J5") (pin "4") (pinfunction "4_4") (pintype "passive"))
    )
    (net (code "24") (name "/MOSI_3.3V") (class "Default")
      (node (ref "IC6") (pin "2") (pinfunction "O_2") (pintype "output"))
      (node (ref "IC7") (pin "28") (pinfunction "MOSI/SDA/HSU_TX_28") (pintype "bidirectional"))
      (node (ref "J6") (pin "3") (pinfunction "DATA_IN_3") (pintype "input"))
    )
    (net (code "25") (name "/RXD") (class "Default")
      (node (ref "IC4") (pin "30") (pinfunction "PD0(RXD)_30") (pintype "bidirectional"))
      (node (ref "J3") (pin "3") (pinfunction "TXO_3") (pintype "passive"))
    )
    (net (code "26") (name "/RXIN") (class "Default")
      (node (ref "IC3") (pin "6") (pinfunction "RXIN_6") (pintype "bidirectional"))
      (node (ref "R13") (pin "2") (pinfunction "2_2") (pintype "passive"))
      (node (ref "U1") (pin "P$2") (pinfunction "RX-_P$2") (pintype "bidirectional"))
    )
    (net (code "27") (name "/RXIP") (class "Default")
      (node (ref "IC3") (pin "5") (pinfunction "RXIP_5") (pintype "bidirectional"))
      (node (ref "R12") (pin "2") (pinfunction "2_2") (pintype "passive"))
      (node (ref "U1") (pin "P$1") (pinfunction "RX+_P$1") (pintype "bidirectional"))
    )
    (net (code "28") (name "/SCK") (class "Default")
      (node (ref "IC3") (pin "30") (pinfunction "SCLK_30") (pintype "bidirectional"))
      (node (ref "IC4") (pin "17") (pinfunction "PB5(SCK)_17") (pintype "bidirectional"))
      (node (ref "IC6") (pin "5") (pinfunction "I_5") (pintype "input"))
      (node (ref "IC6") (pin "9") (pinfunction "I_9") (pintype "input"))
      (node (ref "J5") (pin "3") (pinfunction "3_3") (pintype "passive"))
    )
    (net (code "29") (name "/SCK_3.3V") (class "Default")
      (node (ref "IC6") (pin "4") (pinfunction "O_4") (pintype "output"))
      (node (ref "IC7") (pin "30") (pinfunction "SCK_30") (pintype "bidirectional"))
      (node (ref "J6") (pin "5") (pinfunction "SCLK_5") (pintype "input"))
    )
    (net (code "30") (name "/SEN") (class "Default")
      (node (ref "IC3") (pin "31") (pinfunction "SEN_31") (pintype "bidirectional"))
      (node (ref "Q2") (pin "3") (pinfunction "D_3") (pintype "passive"))
      (node (ref "R16") (pin "2") (pinfunction "2_2") (pintype "passive"))
    )
    (net (code "31") (name "/SOLENOID") (class "Default")
      (node (ref "IC4") (pin "1") (pinfunction "PD3(INT1)_1") (pintype "bidirectional"))
      (node (ref "R17") (pin "1") (pinfunction "1_1") (pintype "passive"))
    )
    (net (code "32") (name "/SPDLED") (class "Default")
      (node (ref "IC3") (pin "67") (pinfunction "SPDLED_67") (pintype "bidirectional"))
      (node (ref "R6") (pin "1") (pinfunction "1_1") (pintype "passive"))
    )
    (net (code "33") (name "/TXD") (class "Default")
      (node (ref "IC4") (pin "31") (pinfunction "PD1(TXD)_31") (pintype "bidirectional"))
      (node (ref "J3") (pin "2") (pinfunction "RXI_2") (pintype "passive"))
    )
    (net (code "34") (name "/TXON") (class "Default")
      (node (ref "IC3") (pin "9") (pinfunction "TXON_9") (pintype "bidirectional"))
      (node (ref "R15") (pin "2") (pinfunction "2_2") (pintype "passive"))
      (node (ref "U1") (pin "P$6") (pinfunction "TX-_P$6") (pintype "bidirectional"))
    )
    (net (code "35") (name "/TXOP") (class "Default")
      (node (ref "IC3") (pin "8") (pinfunction "TXOP_8") (pintype "bidirectional"))
      (node (ref "R14") (pin "2") (pinfunction "2_2") (pintype "passive"))
      (node (ref "U1") (pin "P$5") (pinfunction "TX+_P$5") (pintype "bidirectional"))
    )
    (net (code "36") (name "/W5100_INT") (class "Default")
      (node (ref "IC3") (pin "56") (pinfunction "/INT_56") (pintype "bidirectional"))
      (node (ref "IC4") (pin "32") (pinfunction "PD2(INT0)_32") (pintype "bidirectional"))
    )
    (net (code "37") (name "/WRXLED") (class "Default")
      (node (ref "IC3") (pin "72") (pinfunction "RXLED_72") (pintype "bidirectional"))
      (node (ref "R2") (pin "1") (pinfunction "1_1") (pintype "passive"))
    )
    (net (code "38") (name "/WTXLED") (class "Default")
      (node (ref "IC3") (pin "73") (pinfunction "TXLED_73") (pintype "bidirectional"))
      (node (ref "R1") (pin "1") (pinfunction "1_1") (pintype "passive"))
    )
    (net (code "39") (name "/~{PN532_CS_3V3}") (class "Default")
      (node (ref "IC6") (pin "12") (pinfunction "O_12") (pintype "output"))
      (node (ref "IC7") (pin "27") (pinfunction "NSS/P50_SCL/HSU_RX_27") (pintype "bidirectional"))
    )
    (net (code "40") (name "/~{PN532_CS}") (class "Default")
      (node (ref "IC4") (pin "13") (pinfunction "PB1(OC1A)_13") (pintype "bidirectional"))
      (node (ref "IC6") (pin "11") (pinfunction "I_11") (pintype "input"))
      (node (ref "R29") (pin "2") (pinfunction "2_2") (pintype "passive"))
    )
    (net (code "41") (name "/~{RESET}") (class "Default")
      (node (ref "C16") (pin "2") (pinfunction "2_2") (pintype "passive"))
      (node (ref "IC2") (pin "3") (pinfunction "/MR_3") (pintype "input"))
      (node (ref "IC4") (pin "29") (pinfunction "PC6(/RESET)_29") (pintype "bidirectional"))
      (node (ref "J5") (pin "5") (pinfunction "5_5") (pintype "passive"))
      (node (ref "R19") (pin "1") (pinfunction "1_1") (pintype "passive"))
    )
    (net (code "42") (name "/~{SD_CD}") (class "Default")
      (node (ref "IC4") (pin "2") (pinfunction "PD4(XCK/T0)_2") (pintype "bidirectional"))
      (node (ref "J6") (pin "CD1") (pinfunction "CARD_DETECT_CD1") (pintype "passive"))
      (node (ref "R28") (pin "1") (pinfunction "1_1") (pintype "passive"))
    )
    (net (code "43") (name "/~{SD_CS}") (class "Default")
      (node (ref "IC4") (pin "12") (pinfunction "PB0(ICP)_12") (pintype "bidirectional"))
      (node (ref "IC6") (pin "7") (pinfunction "I_7") (pintype "input"))
      (node (ref "R34") (pin "1") (pinfunction "1_1") (pintype "passive"))
    )
    (net (code "44") (name "/~{W5100_CS}") (class "Default")
      (node (ref "IC3") (pin "29") (pinfunction "/SCS_29") (pintype "bidirectional"))
      (node (ref "IC4") (pin "14") (pinfunction "PB2(SS/OC1B)_14") (pintype "bidirectional"))
      (node (ref "Q2") (pin "1") (pinfunction "G_1") (pintype "passive"))
    )
    (net (code "45") (name "/~{W5100_RESET}") (class "Default")
      (node (ref "IC2") (pin "2") (pinfunction "/RESET_2") (pintype "output"))
      (node (ref "IC3") (pin "59") (pinfunction "/RESET_59") (pintype "bidirectional"))
    )
    (net (code "46") (name "GND") (class "Default")
      (node (ref "C1") (pin "2") (pinfunction "2_2") (pintype "passive"))
      (node (ref "C10") (pin "2") (pinfunction "2_2") (pintype "passive"))
      (node (ref "C11") (pin "2") (pinfunction "2_2") (pintype "passive"))
      (node (ref "C12") (pin "2") (pinfunction "2_2") (pintype "passive"))
      (node (ref "C13") (pin "2") (pinfunction "2_2") (pintype "passive"))
      (node (ref "C14") (pin "2") (pinfunction "2_2") (pintype "passive"))
      (node (ref "C15") (pin "2") (pinfunction "2_2") (pintype "passive"))
      (node (ref "C17") (pin "-") (pinfunction "-_-") (pintype "passive"))
      (node (ref "C18") (pin "2") (pinfunction "2_2") (pintype "passive"))
      (node (ref "C19") (pin "2") (pinfunction "2_2") (pintype "passive"))
      (node (ref "C2") (pin "2") (pinfunction "2_2") (pintype "passive"))
      (node (ref "C20") (pin "2") (pinfunction "2_2") (pintype "passive"))
      (node (ref "C21") (pin "2") (pinfunction "2_2") (pintype "passive"))
      (node (ref "C22") (pin "2") (pinfunction "2_2") (pintype "passive"))
      (node (ref "C23") (pin "2") (pinfunction "2_2") (pintype "passive"))
      (node (ref "C24") (pin "1") (pinfunction "1_1") (pintype "passive"))
      (node (ref "C25") (pin "1") (pinfunction "1_1") (pintype "passive"))
      (node (ref "C28") (pin "1") (pinfunction "1_1") (pintype "passive"))
      (node (ref "C29") (pin "2") (pinfunction "2_2") (pintype "passive"))
      (node (ref "C3") (pin "2") (pinfunction "2_2") (pintype "passive"))
      (node (ref "C33") (pin "2") (pinfunction "2_2") (pintype "passive"))
      (node (ref "C34") (pin "2") (pinfunction "2_2") (pintype "passive"))
      (node (ref "C35") (pin "2") (pinfunction "2_2") (pintype "passive"))
      (node (ref "C36") (pin "2") (pinfunction "2_2") (pintype "passive"))
      (node (ref "C37") (pin "2") (pinfunction "2_2") (pintype "passive"))
      (node (ref "C38") (pin "2") (pinfunction "2_2") (pintype "passive"))
      (node (ref "C39") (pin "2") (pinfunction "2_2") (pintype "passive"))
      (node (ref "C4") (pin "2") (pinfunction "2_2") (pintype "passive"))
      (node (ref "C40") (pin "2") (pinfunction "2_2") (pintype "passive"))
      (node (ref "C41") (pin "2") (pinfunction "2_2") (pintype "passive"))
      (node (ref "C42") (pin "2") (pinfunction "2_2") (pintype "passive"))
      (node (ref "C43") (pin "2") (pinfunction "2_2") (pintype "passive"))
      (node (ref "C44") (pin "2") (pinfunction "2_2") (pintype "passive"))
      (node (ref "C45") (pin "2") (pinfunction "2_2") (pintype "passive"))
      (node (ref "C46") (pin "2") (pinfunction "2_2") (pintype "passive"))
      (node (ref "C47") (pin "2") (pinfunction "2_2") (pintype "passive"))
      (node (ref "C48") (pin "2") (pinfunction "2_2") (pintype "passive"))
      (node (ref "C5") (pin "2") (pinfunction "2_2") (pintype "passive"))
      (node (ref "C6") (pin "1") (pinfunction "1_1") (pintype "passive"))
      (node (ref "C7") (pin "1") (pinfunction "1_1") (pintype "passive"))
      (node (ref "C8") (pin "2") (pinfunction "2_2") (pintype "passive"))
      (node (ref "C9") (pin "2") (pinfunction "2_2") (pintype "passive"))
      (node (ref "D2") (pin "A") (pinfunction "A_A") (pintype "passive"))
      (node (ref "IC1") (pin "1") (pinfunction "GND_1") (pintype "power_in"))
      (node (ref "IC2") (pin "1") (pinfunction "GND_1") (pintype "power_in"))
      (node (ref "IC3") (pin "10") (pinfunction "GNDA1_10") (pintype "bidirectional"))
      (node (ref "IC3") (pin "13") (pinfunction "GNDD0_13") (pintype "bidirectional"))
      (node (ref "IC3") (pin "14") (pinfunction "GNDD1_14") (pintype "bidirectional"))
      (node (ref "IC3") (pin "17") (pinfunction "GNDD2_17") (pintype "bidirectional"))
      (node (ref "IC3") (pin "19") (pinfunction "DATA7_19") (pintype "bidirectional"))
      (node (ref "IC3") (pin "20") (pinfunction "DATA6_20") (pintype "bidirectional"))
      (node (ref "IC3") (pin "21") (pinfunction "DATA5_21") (pintype "bidirectional"))
      (node (ref "IC3") (pin "22") (pinfunction "DATA4_22") (pintype "bidirectional"))
      (node (ref "IC3") (pin "23") (pinfunction "DATA3_23") (pintype "bidirectional"))
      (node (ref "IC3") (pin "24") (pinfunction "DATA2_24") (pintype "bidirectional"))
      (node (ref "IC3") (pin "25") (pinfunction "DATA1_25") (pintype "bidirectional"))
      (node (ref "IC3") (pin "26") (pinfunction "DATA0_26") (pintype "bidirectional"))
      (node (ref "IC3") (pin "32") (pinfunction "GNDD3_32") (pintype "bidirectional"))
      (node (ref "IC3") (pin "34") (pinfunction "TEST_MODE3_34") (pintype "bidirectional"))
      (node (ref "IC3") (pin "35") (pinfunction "TEST_MODE2_35") (pintype "bidirectional"))
      (node (ref "IC3") (pin "36") (pinfunction "TEST_MODE1_36") (pintype "bidirectional"))
      (node (ref "IC3") (pin "37") (pinfunction "TEST_MODE0_37") (pintype "bidirectional"))
      (node (ref "IC3") (pin "38") (pinfunction "ADDR14_38") (pintype "bidirectional"))
      (node (ref "IC3") (pin "39") (pinfunction "ADDR13_39") (pintype "bidirectional"))
      (node (ref "IC3") (pin "4") (pinfunction "GNDA0_4") (pintype "bidirectional"))
      (node (ref "IC3") (pin "40") (pinfunction "ADDR12_40") (pintype "bidirectional"))
      (node (ref "IC3") (pin "41") (pinfunction "ADDR11_41") (pintype "bidirectional"))
      (node (ref "IC3") (pin "42") (pinfunction "ADDR10_42") (pintype "bidirectional"))
      (node (ref "IC3") (pin "43") (pinfunction "GNDD4_43") (pintype "bidirectional"))
      (node (ref "IC3") (pin "45") (pinfunction "ADDR9_45") (pintype "bidirectional"))
      (node (ref "IC3") (pin "46") (pinfunction "ADDR8_46") (pintype "bidirectional"))
      (node (ref "IC3") (pin "47") (pinfunction "ADDR7_47") (pintype "bidirectional"))
      (node (ref "IC3") (pin "48") (pinfunction "ADDR6_48") (pintype "bidirectional"))
      (node (ref "IC3") (pin "49") (pinfunction "ADDR5_49") (pintype "bidirectional"))
      (node (ref "IC3") (pin "50") (pinfunction "ADDR4_50") (pintype "bidirectional"))
      (node (ref "IC3") (pin "51") (pinfunction "ADDR3_51") (pintype "bidirectional"))
      (node (ref "IC3") (pin "52") (pinfunction "ADDR2_52") (pintype "bidirectional"))
      (node (ref "IC3") (pin "53") (pinfunction "ADDR1_53") (pintype "bidirectional"))
      (node (ref "IC3") (pin "54") (pinfunction "ADDR0_54") (pintype "bidirectional"))
      (node (ref "IC3") (pin "63") (pinfunction "OPMODE0_63") (pintype "bidirectional"))
      (node (ref "IC3") (pin "64") (pinfunction "OPMODE1_64") (pintype "bidirectional"))
      (node (ref "IC3") (pin "65") (pinfunction "OPMODE2_65") (pintype "bidirectional"))
      (node (ref "IC3") (pin "68") (pinfunction "GNDD5_68") (pintype "bidirectional"))
      (node (ref "IC3") (pin "77") (pinfunction "GNDA2_77") (pintype "bidirectional"))
      (node (ref "IC4") (pin "21") (pinfunction "AGND_21") (pintype "bidirectional"))
      (node (ref "IC4") (pin "3") (pinfunction "GND_3") (pintype "bidirectional"))
      (node (ref "IC4") (pin "5") (pinfunction "GND_5") (pintype "bidirectional"))
      (node (ref "IC5") (pin "4") (pinfunction "GND_4") (pintype "bidirectional"))
      (node (ref "IC6") (pin "14") (pinfunction "I_14") (pintype "input"))
      (node (ref "IC6") (pin "8") (pinfunction "VSS_8") (pintype "power_in"))
      (node (ref "IC7") (pin "1") (pinfunction "DGND_1") (pintype "bidirectional"))
      (node (ref "IC7") (pin "11") (pinfunction "AGND_11") (pintype "bidirectional"))
      (node (ref "IC7") (pin "16") (pinfunction "I0_16") (pintype "bidirectional"))
      (node (ref "IC7") (pin "17") (pinfunction "I1_17") (pintype "bidirectional"))
      (node (ref "IC7") (pin "18") (pinfunction "TESTEN_18") (pintype "bidirectional"))
      (node (ref "IC7") (pin "3") (pinfunction "TGND1_3") (pintype "bidirectional"))
      (node (ref "IC7") (pin "7") (pinfunction "TGND2_7") (pintype "bidirectional"))
      (node (ref "IC7") (pin "TP") (pinfunction "THERMAL_TP") (pintype "bidirectional"))
      (node (ref "J3") (pin "5") (pinfunction "CTS_5") (pintype "passive"))
      (node (ref "J3") (pin "6") (pinfunction "GND_6") (pintype "passive"))
      (node (ref "J4") (pin "GND") (pinfunction "GND_GND") (pintype "bidirectional"))
      (node (ref "J5") (pin "6") (pinfunction "6_6") (pintype "passive"))
      (node (ref "J6") (pin "6") (pinfunction "VSS_6") (pintype "power_in"))
      (node (ref "J6") (pin "MT1") (pinfunction "GND_MT1") (pintype "power_in"))
      (node (ref "J6") (pin "MT2") (pinfunction "GND1_MT2") (pintype "power_in"))
      (node (ref "LED7") (pin "C") (pinfunction "C_C") (pintype "passive"))
      (node (ref "LED8") (pin "C") (pinfunction "C_C") (pintype "passive"))
      (node (ref "LED9") (pin "C") (pinfunction "C_C") (pintype "passive"))
      (node (ref "Q2") (pin "2") (pinfunction "S_2") (pintype "passive"))
      (node (ref "Q4") (pin "1") (pinfunction "S_1") (pintype "passive"))
      (node (ref "Q4") (pin "2") (pinfunction "S_2") (pintype "passive"))
      (node (ref "Q4") (pin "3") (pinfunction "S_3") (pintype "passive"))
      (node (ref "Q5") (pin "2") (pinfunction "S_2") (pintype "passive"))
      (node (ref "R10") (pin "1") (pinfunction "1_1") (pintype "passive"))
      (node (ref "R20") (pin "2") (pinfunction "2_2") (pintype "passive"))
      (node (ref "R21") (pin "1") (pinfunction "1_1") (pintype "passive"))
      (node (ref "R26") (pin "2") (pinfunction "2_2") (pintype "passive"))
      (node (ref "R33") (pin "1") (pinfunction "1_1") (pintype "passive"))
      (node (ref "R35") (pin "2") (pinfunction "2_2") (pintype "passive"))
      (node (ref "TP3") (pin "P$1") (pinfunction "P$1_P$1") (pintype "bidirectional"))
      (node (ref "TP5") (pin "P$1") (pinfunction "P$1_P$1") (pintype "bidirectional"))
      (node (ref "U1") (pin "GND1") (pinfunction "GND1_GND1") (pintype "bidirectional"))
      (node (ref "U1") (pin "GND2") (pinfunction "GND2_GND2") (pintype "bidirectional"))
      (node (ref "U1") (pin "P$10") (pinfunction "V-_P$10") (pintype "bidirectional"))
    )
    (net (code "47") (name "Net-(C9-Pad1)") (class "Default")
      (node (ref "C9") (pin "1") (pinfunction "1_1") (pintype "passive"))
      (node (ref "R12") (pin "1") (pinfunction "1_1") (pintype "passive"))
      (node (ref "R13") (pin "1") (pinfunction "1_1") (pintype "passive"))
    )
    (net (code "48") (name "Net-(C10-Pad1)") (class "Default")
      (node (ref "C10") (pin "1") (pinfunction "1_1") (pintype "passive"))
      (node (ref "R14") (pin "1") (pinfunction "1_1") (pintype "passive"))
      (node (ref "R15") (pin "1") (pinfunction "1_1") (pintype "passive"))
    )
    (net (code "49") (name "Net-(C24-Pad2)") (class "Default")
      (node (ref "C24") (pin "2") (pinfunction "2_2") (pintype "passive"))
      (node (ref "C25") (pin "2") (pinfunction "2_2") (pintype "passive"))
      (node (ref "C26") (pin "2") (pinfunction "2_2") (pintype "passive"))
      (node (ref "C27") (pin "2") (pinfunction "2_2") (pintype "passive"))
      (node (ref "R31") (pin "2") (pinfunction "2_2") (pintype "passive"))
    )
    (net (code "50") (name "Net-(C26-Pad1)") (class "Default")
      (node (ref "C26") (pin "1") (pinfunction "1_1") (pintype "passive"))
      (node (ref "C27") (pin "1") (pinfunction "1_1") (pintype "passive"))
      (node (ref "C28") (pin "2") (pinfunction "2_2") (pintype "passive"))
      (node (ref "L4") (pin "1") (pinfunction "1_1") (pintype "passive"))
      (node (ref "TP4") (pin "P$1") (pinfunction "P$1_P$1") (pintype "bidirectional"))
    )
    (net (code "51") (name "Net-(C30-Pad1)") (class "Default")
      (node (ref "C30") (pin "1") (pinfunction "1_1") (pintype "passive"))
      (node (ref "R37") (pin "2") (pinfunction "2_2") (pintype "passive"))
    )
    (net (code "52") (name "Net-(C31-Pad1)") (class "Default")
      (node (ref "C31") (pin "1") (pinfunction "1_1") (pintype "passive"))
      (node (ref "C32") (pin "1") (pinfunction "1_1") (pintype "passive"))
      (node (ref "C39") (pin "1") (pinfunction "1_1") (pintype "passive"))
      (node (ref "C40") (pin "1") (pinfunction "1_1") (pintype "passive"))
      (node (ref "R38") (pin "1") (pinfunction "1_1") (pintype "passive"))
    )
    (net (code "53") (name "Net-(C31-Pad2)") (class "Default")
      (node (ref "C31") (pin "2") (pinfunction "2_2") (pintype "passive"))
      (node (ref "C32") (pin "2") (pinfunction "2_2") (pintype "passive"))
      (node (ref "C33") (pin "1") (pinfunction "1_1") (pintype "passive"))
      (node (ref "L7") (pin "1") (pinfunction "1_1") (pintype "passive"))
      (node (ref "R37") (pin "1") (pinfunction "1_1") (pintype "passive"))
      (node (ref "TP2") (pin "P$1") (pinfunction "P$1_P$1") (pintype "bidirectional"))
      (node (ref "TP7") (pin "P$1") (pinfunction "P$1_P$1") (pintype "bidirectional"))
    )
    (net (code "54") (name "Net-(D1-A)") (class "Default")
      (node (ref "D1") (pin "2") (pinfunction "A_2") (pintype "passive"))
      (node (ref "J2") (pin "2") (pinfunction "KL_2") (pintype "passive"))
      (node (ref "Q4") (pin "MB") (pinfunction "D_MB") (pintype "passive"))
    )
    (net (code "55") (name "Net-(IC3-RSET_BG)") (class "Default")
      (node (ref "IC3") (pin "1") (pinfunction "RSET_BG_1") (pintype "bidirectional"))
      (node (ref "R10") (pin "2") (pinfunction "2_2") (pintype "passive"))
    )
    (net (code "56") (name "Net-(IC3-XTLN)") (class "Default")
      (node (ref "C7") (pin "2") (pinfunction "2_2") (pintype "passive"))
      (node (ref "IC3") (pin "75") (pinfunction "XTLN_75") (pintype "bidirectional"))
      (node (ref "Q1") (pin "1") (pinfunction "1_1") (pintype "passive"))
      (node (ref "R5") (pin "2") (pinfunction "2_2") (pintype "passive"))
    )
    (net (code "57") (name "Net-(IC3-XTLP)") (class "Default")
      (node (ref "C6") (pin "2") (pinfunction "2_2") (pintype "passive"))
      (node (ref "IC3") (pin "76") (pinfunction "XTLP_76") (pintype "bidirectional"))
      (node (ref "Q1") (pin "2") (pinfunction "2_2") (pintype "passive"))
      (node (ref "R5") (pin "1") (pinfunction "1_1") (pintype "passive"))
    )
    (net (code "58") (name "Net-(IC3-{slash}CS)") (class "Default")
      (node (ref "IC3") (pin "55") (pinfunction "/CS_55") (pintype "bidirectional"))
      (node (ref "IC3") (pin "57") (pinfunction "/WR_57") (pintype "bidirectional"))
      (node (ref "IC3") (pin "58") (pinfunction "/RD_58") (pintype "bidirectional"))
      (node (ref "R9") (pin "2") (pinfunction "2_2") (pintype "passive"))
    )
    (net (code "59") (name "Net-(IC4-AREF)") (class "Default")
      (node (ref "C23") (pin "1") (pinfunction "1_1") (pintype "passive"))
      (node (ref "IC4") (pin "20") (pinfunction "AREF_20") (pintype "bidirectional"))
    )
    (net (code "60") (name "Net-(IC4-PB6(XTAL1{slash}TOSC1))") (class "Default")
      (node (ref "C20") (pin "1") (pinfunction "1_1") (pintype "passive"))
      (node (ref "IC4") (pin "7") (pinfunction "PB6(XTAL1/TOSC1)_7") (pintype "bidirectional"))
      (node (ref "Q6") (pin "2") (pinfunction "2_2") (pintype "passive"))
    )
    (net (code "61") (name "Net-(IC4-PB7(XTAL2{slash}TOSC2))") (class "Default")
      (node (ref "C21") (pin "1") (pinfunction "1_1") (pintype "passive"))
      (node (ref "IC4") (pin "8") (pinfunction "PB7(XTAL2/TOSC2)_8") (pintype "bidirectional"))
      (node (ref "Q6") (pin "1") (pinfunction "1_1") (pintype "passive"))
    )
    (net (code "62") (name "Net-(IC5-COMP)") (class "Default")
      (node (ref "IC5") (pin "5") (pinfunction "COMP_5") (pintype "bidirectional"))
      (node (ref "R26") (pin "1") (pinfunction "1_1") (pintype "passive"))
      (node (ref "R27") (pin "2") (pinfunction "2_2") (pintype "passive"))
    )
    (net (code "63") (name "Net-(IC5-DVR)") (class "Default")
      (node (ref "IC5") (pin "1") (pinfunction "SWC_1") (pintype "bidirectional"))
      (node (ref "IC5") (pin "7") (pinfunction "SEN_7") (pintype "bidirectional"))
      (node (ref "IC5") (pin "8") (pinfunction "DVR_8") (pintype "bidirectional"))
      (node (ref "R22") (pin "2") (pinfunction "2_2") (pintype "passive"))
    )
    (net (code "64") (name "Net-(IC5-SWE)") (class "Default")
      (node (ref "D2") (pin "C") (pinfunction "C_C") (pintype "passive"))
      (node (ref "IC5") (pin "2") (pinfunction "SWE_2") (pintype "bidirectional"))
      (node (ref "L3") (pin "P$1") (pinfunction "1_P$1") (pintype "passive"))
    )
    (net (code "65") (name "Net-(IC5-TC)") (class "Default")
      (node (ref "C19") (pin "1") (pinfunction "1_1") (pintype "passive"))
      (node (ref "IC5") (pin "3") (pinfunction "TC_3") (pintype "bidirectional"))
    )
    (net (code "66") (name "Net-(IC6C-O)") (class "Default")
      (node (ref "IC6") (pin "6") (pinfunction "O_6") (pintype "output"))
      (node (ref "J6") (pin "2") (pinfunction "CS_2") (pintype "input"))
      (node (ref "LED10") (pin "C") (pinfunction "C_C") (pintype "passive"))
    )
    (net (code "67") (name "Net-(IC6D-O)") (class "Default")
      (node (ref "IC6") (pin "10") (pinfunction "O_10") (pintype "output"))
      (node (ref "R32") (pin "2") (pinfunction "2_2") (pintype "passive"))
    )
    (net (code "68") (name "Net-(IC7-AVDD)") (class "Default")
      (node (ref "C37") (pin "1") (pinfunction "1_1") (pintype "passive"))
      (node (ref "C38") (pin "1") (pinfunction "1_1") (pintype "passive"))
      (node (ref "IC7") (pin "8") (pinfunction "AVDD_8") (pintype "bidirectional"))
      (node (ref "L6") (pin "1") (pinfunction "1_1") (pintype "passive"))
    )
    (net (code "69") (name "Net-(IC7-RSTPD_N)") (class "Default")
      (node (ref "IC7") (pin "38") (pinfunction "RSTPD_N_38") (pintype "bidirectional"))
      (node (ref "R30") (pin "2") (pinfunction "2_2") (pintype "passive"))
    )
    (net (code "70") (name "Net-(IC7-RX)") (class "Default")
      (node (ref "C30") (pin "2") (pinfunction "2_2") (pintype "passive"))
      (node (ref "IC7") (pin "10") (pinfunction "RX_10") (pintype "bidirectional"))
      (node (ref "R36") (pin "1") (pinfunction "1_1") (pintype "passive"))
    )
    (net (code "71") (name "Net-(IC7-TVDD)") (class "Default")
      (node (ref "C35") (pin "1") (pinfunction "1_1") (pintype "passive"))
      (node (ref "C36") (pin "1") (pinfunction "1_1") (pintype "passive"))
      (node (ref "IC7") (pin "5") (pinfunction "TVDD_5") (pintype "bidirectional"))
      (node (ref "L5") (pin "1") (pinfunction "1_1") (pintype "passive"))
    )
    (net (code "72") (name "Net-(IC7-TX1)") (class "Default")
      (node (ref "IC7") (pin "4") (pinfunction "TX1_4") (pintype "bidirectional"))
      (node (ref "L4") (pin "2") (pinfunction "2_2") (pintype "passive"))
    )
    (net (code "73") (name "Net-(IC7-TX2)") (class "Default")
      (node (ref "IC7") (pin "6") (pinfunction "TX2_6") (pintype "bidirectional"))
      (node (ref "L7") (pin "2") (pinfunction "2_2") (pintype "passive"))
    )
    (net (code "74") (name "Net-(IC7-VMID)") (class "Default")
      (node (ref "C29") (pin "1") (pinfunction "1_1") (pintype "passive"))
      (node (ref "IC7") (pin "9") (pinfunction "VMID_9") (pintype "bidirectional"))
      (node (ref "R36") (pin "2") (pinfunction "2_2") (pintype "passive"))
    )
    (net (code "75") (name "Net-(IC7-XTAL1)") (class "Default")
      (node (ref "C47") (pin "1") (pinfunction "1_1") (pintype "passive"))
      (node (ref "IC7") (pin "14") (pinfunction "XTAL1_14") (pintype "bidirectional"))
      (node (ref "Q7") (pin "1") (pinfunction "1_1") (pintype "passive"))
    )
    (net (code "76") (name "Net-(IC7-XTAL2)") (class "Default")
      (node (ref "C48") (pin "1") (pinfunction "1_1") (pintype "passive"))
      (node (ref "IC7") (pin "15") (pinfunction "XTAL2_15") (pintype "bidirectional"))
      (node (ref "Q7") (pin "3") (pinfunction "2_3") (pintype "passive"))
    )
    (net (code "77") (name "Net-(J3-DTR)") (class "Default")
      (node (ref "C16") (pin "1") (pinfunction "1_1") (pintype "passive"))
      (node (ref "J3") (pin "1") (pinfunction "DTR_1") (pintype "passive"))
    )
    (net (code "78") (name "Net-(LED1-PadC)") (class "Default")
      (node (ref "LED1") (pin "C") (pinfunction "C_C") (pintype "passive"))
      (node (ref "R1") (pin "2") (pinfunction "2_2") (pintype "passive"))
    )
    (net (code "79") (name "Net-(LED2-PadC)") (class "Default")
      (node (ref "LED2") (pin "C") (pinfunction "C_C") (pintype "passive"))
      (node (ref "R2") (pin "2") (pinfunction "2_2") (pintype "passive"))
    )
    (net (code "80") (name "Net-(LED3-PadC)") (class "Default")
      (node (ref "LED3") (pin "C") (pinfunction "C_C") (pintype "passive"))
      (node (ref "R3") (pin "2") (pinfunction "2_2") (pintype "passive"))
    )
    (net (code "81") (name "Net-(LED4-PadC)") (class "Default")
      (node (ref "LED4") (pin "C") (pinfunction "C_C") (pintype "passive"))
      (node (ref "R4") (pin "2") (pinfunction "2_2") (pintype "passive"))
    )
    (net (code "82") (name "Net-(LED5-PadC)") (class "Default")
      (node (ref "LED5") (pin "C") (pinfunction "C_C") (pintype "passive"))
      (node (ref "R6") (pin "2") (pinfunction "2_2") (pintype "passive"))
    )
    (net (code "83") (name "Net-(LED6-PadC)") (class "Default")
      (node (ref "LED6") (pin "C") (pinfunction "C_C") (pintype "passive"))
      (node (ref "R7") (pin "2") (pinfunction "2_2") (pintype "passive"))
    )
    (net (code "84") (name "Net-(LED7-PadA)") (class "Default")
      (node (ref "LED7") (pin "A") (pinfunction "A_A") (pintype "passive"))
      (node (ref "R23") (pin "2") (pinfunction "2_2") (pintype "passive"))
    )
    (net (code "85") (name "Net-(LED8-PadA)") (class "Default")
      (node (ref "LED8") (pin "A") (pinfunction "A_A") (pintype "passive"))
      (node (ref "R24") (pin "2") (pinfunction "2_2") (pintype "passive"))
    )
    (net (code "86") (name "Net-(LED9-PadA)") (class "Default")
      (node (ref "LED9") (pin "A") (pinfunction "A_A") (pintype "passive"))
      (node (ref "R25") (pin "1") (pinfunction "1_1") (pintype "passive"))
    )
    (net (code "87") (name "Net-(LED10-PadA)") (class "Default")
      (node (ref "LED10") (pin "A") (pinfunction "A_A") (pintype "passive"))
      (node (ref "R32") (pin "1") (pinfunction "1_1") (pintype "passive"))
    )
    (net (code "88") (name "Net-(Q4-G)") (class "Default")
      (node (ref "Q4") (pin "4") (pinfunction "G_4") (pintype "passive"))
      (node (ref "R17") (pin "2") (pinfunction "2_2") (pintype "passive"))
      (node (ref "R20") (pin "1") (pinfunction "1_1") (pintype "passive"))
    )
    (net (code "89") (name "Net-(Q5-D)") (class "Default")
      (node (ref "Q3") (pin "-") (pinfunction "-_-") (pintype "passive"))
      (node (ref "Q5") (pin "3") (pinfunction "D_3") (pintype "passive"))
    )
    (net (code "90") (name "Net-(Q5-G)") (class "Default")
      (node (ref "Q5") (pin "1") (pinfunction "G_1") (pintype "passive"))
      (node (ref "R18") (pin "2") (pinfunction "2_2") (pintype "passive"))
      (node (ref "R21") (pin "2") (pinfunction "2_2") (pintype "passive"))
    )
    (net (code "91") (name "Net-(R31-Pad1)") (class "Default")
      (node (ref "R31") (pin "1") (pinfunction "1_1") (pintype "passive"))
      (node (ref "R33") (pin "2") (pinfunction "2_2") (pintype "passive"))
      (node (ref "TP1") (pin "P$1") (pinfunction "P$1_P$1") (pintype "bidirectional"))
    )
    (net (code "92") (name "Net-(R35-Pad1)") (class "Default")
      (node (ref "R35") (pin "1") (pinfunction "1_1") (pintype "passive"))
      (node (ref "R38") (pin "2") (pinfunction "2_2") (pintype "passive"))
      (node (ref "TP6") (pin "P$1") (pinfunction "P$1_P$1") (pintype "bidirectional"))
    )
    (net (code "93") (name "Net-(U1-G-)") (class "Default")
      (node (ref "R8") (pin "1") (pinfunction "1_1") (pintype "passive"))
      (node (ref "U1") (pin "P$14") (pinfunction "G-_P$14") (pintype "bidirectional"))
    )
    (net (code "94") (name "Net-(U1-V+)") (class "Default")
      (node (ref "J1") (pin "1") (pinfunction "1_1") (pintype "passive"))
      (node (ref "U1") (pin "P$9") (pinfunction "V+_P$9") (pintype "bidirectional"))
    )
    (net (code "95") (name "Net-(U1-Y-)") (class "Default")
      (node (ref "R11") (pin "1") (pinfunction "1_1") (pintype "passive"))
      (node (ref "U1") (pin "P$12") (pinfunction "Y-_P$12") (pintype "bidirectional"))
    )
    (net (code "96") (name "unconnected-(IC3-NC0-Pad3)") (class "Default")
      (node (ref "IC3") (pin "3") (pinfunction "NC0_3") (pintype "bidirectional"))
    )
    (net (code "97") (name "unconnected-(IC3-NC1-Pad60)") (class "Default")
      (node (ref "IC3") (pin "60") (pinfunction "NC1_60") (pintype "bidirectional"))
    )
    (net (code "98") (name "unconnected-(IC3-NC2-Pad61)") (class "Default")
      (node (ref "IC3") (pin "61") (pinfunction "NC2_61") (pintype "bidirectional"))
    )
    (net (code "99") (name "unconnected-(IC3-NC3-Pad62)") (class "Default")
      (node (ref "IC3") (pin "62") (pinfunction "NC3_62") (pintype "bidirectional"))
    )
    (net (code "100") (name "unconnected-(IC3-NC4-Pad78)") (class "Default")
      (node (ref "IC3") (pin "78") (pinfunction "NC4_78") (pintype "bidirectional"))
    )
    (net (code "101") (name "unconnected-(IC3-NC5-Pad79)") (class "Default")
      (node (ref "IC3") (pin "79") (pinfunction "NC5_79") (pintype "bidirectional"))
    )
    (net (code "102") (name "unconnected-(IC3-NC6-Pad80)") (class "Default")
      (node (ref "IC3") (pin "80") (pinfunction "NC6_80") (pintype "bidirectional"))
    )
    (net (code "103") (name "unconnected-(IC6F-O-Pad15)") (class "Default")
      (node (ref "IC6") (pin "15") (pinfunction "O_15") (pintype "output"))
    )
    (net (code "104") (name "unconnected-(IC7-AUX1-Pad12)") (class "Default")
      (node (ref "IC7") (pin "12") (pinfunction "AUX1_12") (pintype "bidirectional"))
    )
    (net (code "105") (name "unconnected-(IC7-AUX2-Pad13)") (class "Default")
      (node (ref "IC7") (pin "13") (pinfunction "AUX2_13") (pintype "bidirectional"))
    )
    (net (code "106") (name "unconnected-(IC7-IRQ-Pad25)") (class "Default")
      (node (ref "IC7") (pin "25") (pinfunction "IRQ_25") (pintype "bidirectional"))
    )
    (net (code "107") (name "unconnected-(IC7-LOADMOD-Pad2)") (class "Default")
      (node (ref "IC7") (pin "2") (pinfunction "LOADMOD_2") (pintype "bidirectional"))
    )
    (net (code "108") (name "unconnected-(IC7-NC1-Pad20)") (class "Default")
      (node (ref "IC7") (pin "20") (pinfunction "NC1_20") (pintype "bidirectional"))
    )
    (net (code "109") (name "unconnected-(IC7-NC2-Pad21)") (class "Default")
      (node (ref "IC7") (pin "21") (pinfunction "NC2_21") (pintype "bidirectional"))
    )
    (net (code "110") (name "unconnected-(IC7-NC3-Pad22)") (class "Default")
      (node (ref "IC7") (pin "22") (pinfunction "NC3_22") (pintype "bidirectional"))
    )
    (net (code "111") (name "unconnected-(IC7-P30{slash}UART_RX-Pad24)") (class "Default")
      (node (ref "IC7") (pin "24") (pinfunction "P30/UART_RX_24") (pintype "bidirectional"))
    )
    (net (code "112") (name "unconnected-(IC7-P31-Pad31)") (class "Default")
      (node (ref "IC7") (pin "31") (pinfunction "P31_31") (pintype "bidirectional"))
    )
    (net (code "113") (name "unconnected-(IC7-P32-Pad32)") (class "Default")
      (node (ref "IC7") (pin "32") (pinfunction "P32_32") (pintype "bidirectional"))
    )
    (net (code "114") (name "unconnected-(IC7-P33-Pad33)") (class "Default")
      (node (ref "IC7") (pin "33") (pinfunction "P33_33") (pintype "bidirectional"))
    )
    (net (code "115") (name "unconnected-(IC7-P34{slash}SIC_CLK-Pad34)") (class "Default")
      (node (ref "IC7") (pin "34") (pinfunction "P34/SIC_CLK_34") (pintype "bidirectional"))
    )
    (net (code "116") (name "unconnected-(IC7-P35-Pad19)") (class "Default")
      (node (ref "IC7") (pin "19") (pinfunction "P35_19") (pintype "bidirectional"))
    )
    (net (code "117") (name "unconnected-(IC7-RSTOUT_N-Pad26)") (class "Default")
      (node (ref "IC7") (pin "26") (pinfunction "RSTOUT_N_26") (pintype "bidirectional"))
    )
    (net (code "118") (name "unconnected-(IC7-SIGIN-Pad36)") (class "Default")
      (node (ref "IC7") (pin "36") (pinfunction "SIGIN_36") (pintype "bidirectional"))
    )
    (net (code "119") (name "unconnected-(IC7-SIGOUT-Pad35)") (class "Default")
      (node (ref "IC7") (pin "35") (pinfunction "SIGOUT_35") (pintype "bidirectional"))
    )
    (net (code "120") (name "unconnected-(J4-GNDBREAK-PadSW)") (class "Default")
      (node (ref "J4") (pin "SW") (pinfunction "GNDBREAK_SW") (pintype "bidirectional"))
    )
    (net (code "121") (name "unconnected-(J6-CARD_DETECT1-PadCD2)") (class "Default")
      (node (ref "J6") (pin "CD2") (pinfunction "CARD_DETECT1_CD2") (pintype "passive"))
    )
    (net (code "122") (name "unconnected-(J6-DAT1-Pad8)") (class "Default")
      (node (ref "J6") (pin "8") (pinfunction "DAT1_8") (pintype "bidirectional"))
    )
    (net (code "123") (name "unconnected-(J6-DAT2-Pad1)") (class "Default")
      (node (ref "J6") (pin "1") (pinfunction "DAT2_1") (pintype "bidirectional"))
    )
  )
)
